# Main.net
KiCad netlist of a schematic drawn in EAGLE
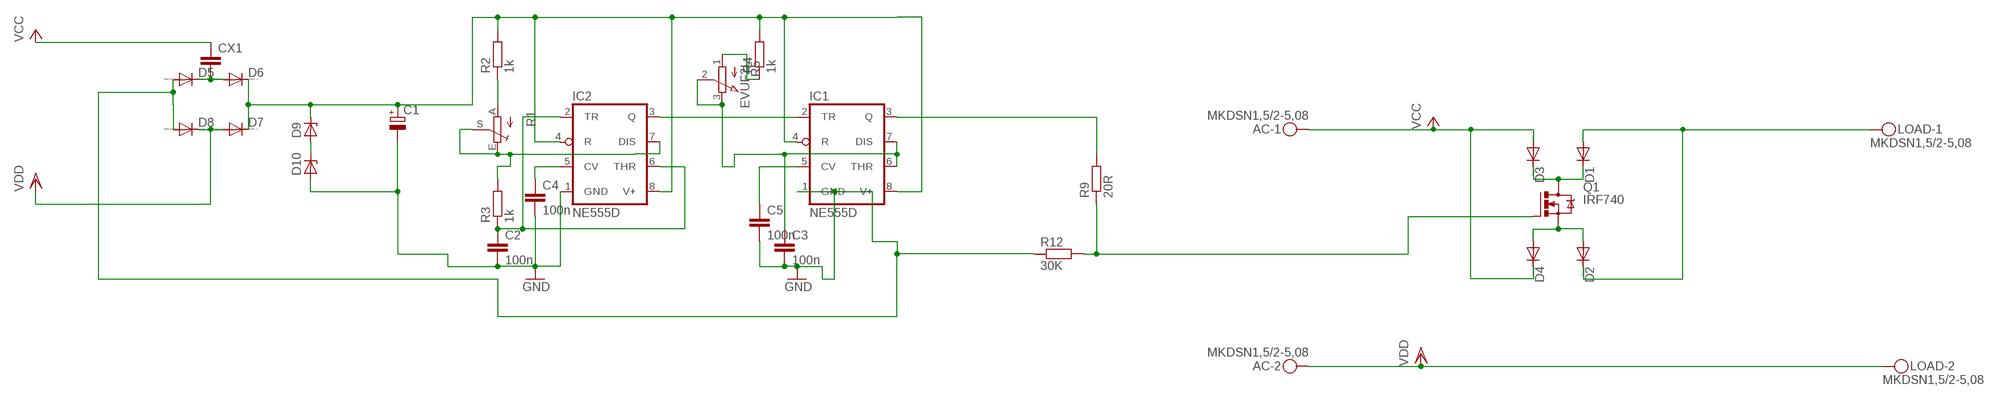
[diagram p0: schematic, sheet 1]

(export (version "E")
  (design (tool "Eeschema 10.0.6"))
  (components
    (comp (ref "AC")
      (value "MKDSN1,5/2-5,08")
      (footprint "eagle-import:MKDSN1,5_2-5,08")
      (libsource (lib "eagle-import") (part "MKDSN1,5/2-5,08"))
    )
    (comp (ref "C1")
      (value "CPOL-EUE2.5-7")
      (footprint "eagle-import:E2,5-7")
      (libsource (lib "eagle-import") (part "CPOL-EUE2.5-7"))
    )
    (comp (ref "C2")
      (value "100n")
      (footprint "eagle-import:C0805")
      (libsource (lib "eagle-import") (part "C-EUC0805"))
    )
    (comp (ref "C3")
      (value "100n")
      (footprint "eagle-import:C0805")
      (libsource (lib "eagle-import") (part "C-EUC0805"))
    )
    (comp (ref "C4")
      (value "100n")
      (footprint "eagle-import:C0805")
      (libsource (lib "eagle-import") (part "C-EUC0805"))
    )
    (comp (ref "C5")
      (value "100n")
      (footprint "eagle-import:C0805")
      (libsource (lib "eagle-import") (part "C-EUC0805"))
    )
    (comp (ref "CX1")
      (value "CXXC15B8")
      (footprint "eagle-import:XC15B8")
      (libsource (lib "eagle-import") (part "CXXC15B8"))
    )
    (comp (ref "D1")
      (value "DIODE-DO220S")
      (footprint "eagle-import:DO220S")
      (libsource (lib "eagle-import") (part "DIODE-DO220S"))
    )
    (comp (ref "D2")
      (value "DIODE-DO220S")
      (footprint "eagle-import:DO220S")
      (libsource (lib "eagle-import") (part "DIODE-DO220S"))
    )
    (comp (ref "D3")
      (value "DIODE-DO220S")
      (footprint "eagle-import:DO220S")
      (libsource (lib "eagle-import") (part "DIODE-DO220S"))
    )
    (comp (ref "D4")
      (value "DIODE-DO220S")
      (footprint "eagle-import:DO220S")
      (libsource (lib "eagle-import") (part "DIODE-DO220S"))
    )
    (comp (ref "D5")
      (value "DIODE-DO-214AC")
      (footprint "eagle-import:DO-214AC")
      (libsource (lib "eagle-import") (part "DIODE-DO-214AC"))
    )
    (comp (ref "D6")
      (value "DIODE-DO-214AC")
      (footprint "eagle-import:DO-214AC")
      (libsource (lib "eagle-import") (part "DIODE-DO-214AC"))
    )
    (comp (ref "D7")
      (value "DIODE-DO-214AC")
      (footprint "eagle-import:DO-214AC")
      (libsource (lib "eagle-import") (part "DIODE-DO-214AC"))
    )
    (comp (ref "D8")
      (value "DIODE-DO-214AC")
      (footprint "eagle-import:DO-214AC")
      (libsource (lib "eagle-import") (part "DIODE-DO-214AC"))
    )
    (comp (ref "D9")
      (value "ZENER-DIODESOD80C")
      (footprint "eagle-import:SOD80C")
      (libsource (lib "eagle-import") (part "ZENER-DIODESOD80C"))
    )
    (comp (ref "D10")
      (value "ZENER-DIODESOD80C")
      (footprint "eagle-import:SOD80C")
      (libsource (lib "eagle-import") (part "ZENER-DIODESOD80C"))
    )
    (comp (ref "IC1")
      (value "NE555D")
      (footprint "eagle-import:SO08")
      (libsource (lib "eagle-import") (part "555DNE"))
    )
    (comp (ref "IC2")
      (value "NE555D")
      (footprint "eagle-import:SO08")
      (libsource (lib "eagle-import") (part "555DNE"))
    )
    (comp (ref "LOAD")
      (value "MKDSN1,5/2-5,08")
      (footprint "eagle-import:MKDSN1,5_2-5,08")
      (libsource (lib "eagle-import") (part "MKDSN1,5/2-5,08"))
    )
    (comp (ref "Q1")
      (value "IRF740")
      (footprint "eagle-import:TO220BV")
      (libsource (lib "eagle-import") (part "IRF740"))
    )
    (comp (ref "R1")
      (value "TRIM_EU-S75H")
      (footprint "eagle-import:S75H")
      (libsource (lib "eagle-import") (part "TRIM_EU-S75H"))
    )
    (comp (ref "R2")
      (value "1k")
      (footprint "eagle-import:R1206")
      (libsource (lib "eagle-import") (part "R-EU_R1206"))
    )
    (comp (ref "R3")
      (value "1k")
      (footprint "eagle-import:R1206")
      (libsource (lib "eagle-import") (part "R-EU_R1206"))
    )
    (comp (ref "R4")
      (value "1k")
      (footprint "eagle-import:R1206")
      (libsource (lib "eagle-import") (part "R-EU_R1206"))
    )
    (comp (ref "R5")
      (value "EVUF2L")
      (footprint "eagle-import:EVUFXL")
      (libsource (lib "eagle-import") (part "EVULF2"))
    )
    (comp (ref "R9")
      (value "20R")
      (footprint "eagle-import:R1206")
      (libsource (lib "eagle-import") (part "R-EU_R1206"))
    )
    (comp (ref "R12")
      (value "30K")
      (footprint "eagle-import:R0805")
      (libsource (lib "eagle-import") (part "R-EU_R0805"))
    )
  )
  (nets
    (net (code "1") (name "GND") (class "Default")
      (node (ref "C1") (pin "-") (pinfunction "-_-") (pintype "passive"))
      (node (ref "C2") (pin "2") (pinfunction "2_2") (pintype "passive"))
      (node (ref "C3") (pin "2") (pinfunction "2_2") (pintype "passive"))
      (node (ref "C4") (pin "2") (pinfunction "2_2") (pintype "passive"))
      (node (ref "C5") (pin "2") (pinfunction "2_2") (pintype "passive"))
      (node (ref "D10") (pin "A") (pinfunction "A_A") (pintype "passive"))
      (node (ref "D5") (pin "A") (pinfunction "A_A") (pintype "passive"))
      (node (ref "D8") (pin "A") (pinfunction "A_A") (pintype "passive"))
      (node (ref "IC1") (pin "1") (pinfunction "GND_1") (pintype "power_in"))
      (node (ref "IC2") (pin "1") (pinfunction "GND_1") (pintype "power_in"))
      (node (ref "R12") (pin "1") (pinfunction "1_1") (pintype "passive"))
    )
    (net (code "2") (name "Net-(CX1-Pad2)") (class "Default")
      (node (ref "CX1") (pin "2") (pinfunction "2_2") (pintype "passive"))
      (node (ref "D5") (pin "C") (pinfunction "C_C") (pintype "passive"))
      (node (ref "D6") (pin "A") (pinfunction "A_A") (pintype "passive"))
    )
    (net (code "3") (name "Net-(D1-PadC)") (class "Default")
      (node (ref "D1") (pin "C") (pinfunction "C_C") (pintype "passive"))
      (node (ref "D3") (pin "C") (pinfunction "C_C") (pintype "passive"))
      (node (ref "Q1") (pin "D") (pinfunction "D_D") (pintype "passive"))
    )
    (net (code "4") (name "Net-(D2-PadA)") (class "Default")
      (node (ref "D2") (pin "A") (pinfunction "A_A") (pintype "passive"))
      (node (ref "D4") (pin "A") (pinfunction "A_A") (pintype "passive"))
      (node (ref "Q1") (pin "S") (pinfunction "S_S") (pintype "passive"))
    )
    (net (code "5") (name "Net-(D10-PadC)") (class "Default")
      (node (ref "D10") (pin "C") (pinfunction "C_C") (pintype "passive"))
      (node (ref "D9") (pin "A") (pinfunction "A_A") (pintype "passive"))
    )
    (net (code "6") (name "Net-(IC1-CV)") (class "Default")
      (node (ref "C5") (pin "1") (pinfunction "1_1") (pintype "passive"))
      (node (ref "IC1") (pin "5") (pinfunction "CV_5") (pintype "input"))
    )
    (net (code "7") (name "Net-(IC1-DIS)") (class "Default")
      (node (ref "C3") (pin "1") (pinfunction "1_1") (pintype "passive"))
      (node (ref "IC1") (pin "6") (pinfunction "THR_6") (pintype "input"))
      (node (ref "IC1") (pin "7") (pinfunction "DIS_7") (pintype "input"))
      (node (ref "R5") (pin "2") (pinfunction "S_2") (pintype "passive"))
      (node (ref "R5") (pin "3") (pinfunction "E_3") (pintype "passive"))
    )
    (net (code "8") (name "Net-(IC1-Q)") (class "Default")
      (node (ref "IC1") (pin "3") (pinfunction "Q_3") (pintype "output"))
      (node (ref "R9") (pin "2") (pinfunction "2_2") (pintype "passive"))
    )
    (net (code "9") (name "Net-(IC1-R)") (class "Default")
      (node (ref "C1") (pin "+") (pinfunction "+_+") (pintype "passive"))
      (node (ref "D6") (pin "C") (pinfunction "C_C") (pintype "passive"))
      (node (ref "D7") (pin "C") (pinfunction "C_C") (pintype "passive"))
      (node (ref "D9") (pin "C") (pinfunction "C_C") (pintype "passive"))
      (node (ref "IC1") (pin "4") (pinfunction "R_4") (pintype "input"))
      (node (ref "IC1") (pin "8") (pinfunction "V+_8") (pintype "power_in"))
      (node (ref "IC2") (pin "4") (pinfunction "R_4") (pintype "input"))
      (node (ref "IC2") (pin "8") (pinfunction "V+_8") (pintype "power_in"))
      (node (ref "R2") (pin "2") (pinfunction "2_2") (pintype "passive"))
      (node (ref "R4") (pin "2") (pinfunction "2_2") (pintype "passive"))
    )
    (net (code "10") (name "Net-(IC1-TR)") (class "Default")
      (node (ref "IC1") (pin "2") (pinfunction "TR_2") (pintype "input"))
      (node (ref "IC2") (pin "3") (pinfunction "Q_3") (pintype "output"))
    )
    (net (code "11") (name "Net-(IC2-CV)") (class "Default")
      (node (ref "C4") (pin "1") (pinfunction "1_1") (pintype "passive"))
      (node (ref "IC2") (pin "5") (pinfunction "CV_5") (pintype "input"))
    )
    (net (code "12") (name "Net-(IC2-DIS)") (class "Default")
      (node (ref "IC2") (pin "7") (pinfunction "DIS_7") (pintype "input"))
      (node (ref "R1") (pin "E") (pinfunction "E_E") (pintype "passive"))
      (node (ref "R1") (pin "S") (pinfunction "S_S") (pintype "passive"))
      (node (ref "R3") (pin "2") (pinfunction "2_2") (pintype "passive"))
    )
    (net (code "13") (name "Net-(IC2-THR)") (class "Default")
      (node (ref "C2") (pin "1") (pinfunction "1_1") (pintype "passive"))
      (node (ref "IC2") (pin "2") (pinfunction "TR_2") (pintype "input"))
      (node (ref "IC2") (pin "6") (pinfunction "THR_6") (pintype "input"))
      (node (ref "R3") (pin "1") (pinfunction "1_1") (pintype "passive"))
    )
    (net (code "14") (name "Net-(LOADA-KL)") (class "Default")
      (node (ref "D1") (pin "A") (pinfunction "A_A") (pintype "passive"))
      (node (ref "D2") (pin "C") (pinfunction "C_C") (pintype "passive"))
      (node (ref "LOAD") (pin "1") (pinfunction "KL_1") (pintype "passive"))
    )
    (net (code "15") (name "Net-(Q1-PadG)") (class "Default")
      (node (ref "Q1") (pin "G") (pinfunction "G_G") (pintype "passive"))
      (node (ref "R12") (pin "2") (pinfunction "2_2") (pintype "passive"))
      (node (ref "R9") (pin "1") (pinfunction "1_1") (pintype "passive"))
    )
    (net (code "16") (name "Net-(R1-PadA)") (class "Default")
      (node (ref "R1") (pin "A") (pinfunction "A_A") (pintype "passive"))
      (node (ref "R2") (pin "1") (pinfunction "1_1") (pintype "passive"))
    )
    (net (code "17") (name "Net-(R5-A)") (class "Default")
      (node (ref "R4") (pin "1") (pinfunction "1_1") (pintype "passive"))
      (node (ref "R5") (pin "1") (pinfunction "A_1") (pintype "passive"))
    )
    (net (code "18") (name "VCC") (class "Default")
      (node (ref "AC") (pin "1") (pinfunction "KL_1") (pintype "passive"))
      (node (ref "CX1") (pin "1") (pinfunction "1_1") (pintype "passive"))
      (node (ref "D3") (pin "A") (pinfunction "A_A") (pintype "passive"))
      (node (ref "D4") (pin "C") (pinfunction "C_C") (pintype "passive"))
    )
    (net (code "19") (name "VDD") (class "Default")
      (node (ref "AC") (pin "2") (pinfunction "KL_2") (pintype "passive"))
      (node (ref "D7") (pin "A") (pinfunction "A_A") (pintype "passive"))
      (node (ref "D8") (pin "C") (pinfunction "C_C") (pintype "passive"))
      (node (ref "LOAD") (pin "2") (pinfunction "KL_2") (pintype "passive"))
    )
  )
)
